# SDRAM.net
KiCad netlist of a schematic drawn in Altium Designer
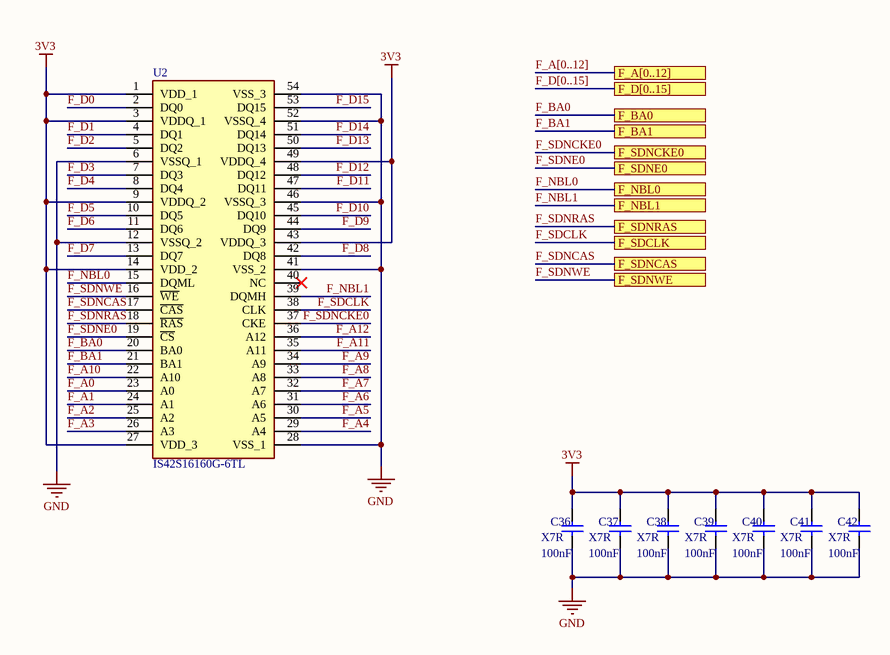
[diagram p0: SDRAM.SchDoc]

(export (version "E")
  (design (tool "Eeschema 10.0.6"))
  (components
    (comp (ref "C36")
      (value "X7R")
      (footprint "1608[0603]")
      (description "Capacitor")
      (fields (field (name "ALTIUM_VALUE") "100nF") (field (name "PUBLISHER") "Altium Limited"))
      (libsource (lib "Miscellaneous Devices") (part "Cap"))
    )
    (comp (ref "C37")
      (value "X7R")
      (footprint "1608[0603]")
      (description "Capacitor")
      (fields (field (name "ALTIUM_VALUE") "100nF") (field (name "PUBLISHER") "Altium Limited"))
      (libsource (lib "Miscellaneous Devices") (part "Cap"))
    )
    (comp (ref "C38")
      (value "X7R")
      (footprint "1608[0603]")
      (description "Capacitor")
      (fields (field (name "ALTIUM_VALUE") "100nF") (field (name "PUBLISHER") "Altium Limited"))
      (libsource (lib "Miscellaneous Devices") (part "Cap"))
    )
    (comp (ref "C39")
      (value "X7R")
      (footprint "1608[0603]")
      (description "Capacitor")
      (fields (field (name "ALTIUM_VALUE") "100nF") (field (name "PUBLISHER") "Altium Limited"))
      (libsource (lib "Miscellaneous Devices") (part "Cap"))
    )
    (comp (ref "C40")
      (value "X7R")
      (footprint "1608[0603]")
      (description "Capacitor")
      (fields (field (name "ALTIUM_VALUE") "100nF") (field (name "PUBLISHER") "Altium Limited"))
      (libsource (lib "Miscellaneous Devices") (part "Cap"))
    )
    (comp (ref "C41")
      (value "X7R")
      (footprint "1608[0603]")
      (description "Capacitor")
      (fields (field (name "ALTIUM_VALUE") "100nF") (field (name "PUBLISHER") "Altium Limited"))
      (libsource (lib "Miscellaneous Devices") (part "Cap"))
    )
    (comp (ref "C42")
      (value "X7R")
      (footprint "1608[0603]")
      (description "Capacitor")
      (fields (field (name "ALTIUM_VALUE") "100nF") (field (name "PUBLISHER") "Altium Limited"))
      (libsource (lib "Miscellaneous Devices") (part "Cap"))
    )
    (comp (ref "U2")
      (value "IS42S16160G-6TL")
      (footprint "SamacSys:SOP80P1176X120-54N")
      (description "Integrated Circuit")
      (fields (field (name "MOUSER PART NUMBER") "870-IS42S16160G-6TL"))
      (libsource (lib "*") (part "IS42S16160G-6TL"))
    )
  )
  (nets
    (net (code "2") (name "/F_A0") (class "Default")
      (node (ref "U2") (pin "23") (pinfunction "A0_23") (pintype "passive"))
    )
    (net (code "3") (name "/F_A1") (class "Default")
      (node (ref "U2") (pin "24") (pinfunction "A1_24") (pintype "passive"))
    )
    (net (code "4") (name "/F_A2") (class "Default")
      (node (ref "U2") (pin "25") (pinfunction "A2_25") (pintype "passive"))
    )
    (net (code "5") (name "/F_A3") (class "Default")
      (node (ref "U2") (pin "26") (pinfunction "A3_26") (pintype "passive"))
    )
    (net (code "6") (name "/F_A4") (class "Default")
      (node (ref "U2") (pin "29") (pinfunction "A4_29") (pintype "passive"))
    )
    (net (code "7") (name "/F_A5") (class "Default")
      (node (ref "U2") (pin "30") (pinfunction "A5_30") (pintype "passive"))
    )
    (net (code "8") (name "/F_A6") (class "Default")
      (node (ref "U2") (pin "31") (pinfunction "A6_31") (pintype "passive"))
    )
    (net (code "9") (name "/F_A7") (class "Default")
      (node (ref "U2") (pin "32") (pinfunction "A7_32") (pintype "passive"))
    )
    (net (code "10") (name "/F_A8") (class "Default")
      (node (ref "U2") (pin "33") (pinfunction "A8_33") (pintype "passive"))
    )
    (net (code "11") (name "/F_A9") (class "Default")
      (node (ref "U2") (pin "34") (pinfunction "A9_34") (pintype "passive"))
    )
    (net (code "12") (name "/F_A10") (class "Default")
      (node (ref "U2") (pin "22") (pinfunction "A10_22") (pintype "passive"))
    )
    (net (code "13") (name "/F_A11") (class "Default")
      (node (ref "U2") (pin "35") (pinfunction "A11_35") (pintype "passive"))
    )
    (net (code "14") (name "/F_A12") (class "Default")
      (node (ref "U2") (pin "36") (pinfunction "A12_36") (pintype "passive"))
    )
    (net (code "16") (name "/F_BA0") (class "Default")
      (node (ref "U2") (pin "20") (pinfunction "BA0_20") (pintype "passive"))
    )
    (net (code "17") (name "/F_BA1") (class "Default")
      (node (ref "U2") (pin "21") (pinfunction "BA1_21") (pintype "passive"))
    )
    (net (code "18") (name "/F_D0") (class "Default")
      (node (ref "U2") (pin "2") (pinfunction "DQ0_2") (pintype "passive"))
    )
    (net (code "19") (name "/F_D1") (class "Default")
      (node (ref "U2") (pin "4") (pinfunction "DQ1_4") (pintype "passive"))
    )
    (net (code "20") (name "/F_D2") (class "Default")
      (node (ref "U2") (pin "5") (pinfunction "DQ2_5") (pintype "passive"))
    )
    (net (code "21") (name "/F_D3") (class "Default")
      (node (ref "U2") (pin "7") (pinfunction "DQ3_7") (pintype "passive"))
    )
    (net (code "22") (name "/F_D4") (class "Default")
      (node (ref "U2") (pin "8") (pinfunction "DQ4_8") (pintype "passive"))
    )
    (net (code "23") (name "/F_D5") (class "Default")
      (node (ref "U2") (pin "10") (pinfunction "DQ5_10") (pintype "passive"))
    )
    (net (code "24") (name "/F_D6") (class "Default")
      (node (ref "U2") (pin "11") (pinfunction "DQ6_11") (pintype "passive"))
    )
    (net (code "25") (name "/F_D7") (class "Default")
      (node (ref "U2") (pin "13") (pinfunction "DQ7_13") (pintype "passive"))
    )
    (net (code "26") (name "/F_D8") (class "Default")
      (node (ref "U2") (pin "42") (pinfunction "DQ8_42") (pintype "passive"))
    )
    (net (code "27") (name "/F_D9") (class "Default")
      (node (ref "U2") (pin "44") (pinfunction "DQ9_44") (pintype "passive"))
    )
    (net (code "28") (name "/F_D10") (class "Default")
      (node (ref "U2") (pin "45") (pinfunction "DQ10_45") (pintype "passive"))
    )
    (net (code "29") (name "/F_D11") (class "Default")
      (node (ref "U2") (pin "47") (pinfunction "DQ11_47") (pintype "passive"))
    )
    (net (code "30") (name "/F_D12") (class "Default")
      (node (ref "U2") (pin "48") (pinfunction "DQ12_48") (pintype "passive"))
    )
    (net (code "31") (name "/F_D13") (class "Default")
      (node (ref "U2") (pin "50") (pinfunction "DQ13_50") (pintype "passive"))
    )
    (net (code "32") (name "/F_D14") (class "Default")
      (node (ref "U2") (pin "51") (pinfunction "DQ14_51") (pintype "passive"))
    )
    (net (code "33") (name "/F_D15") (class "Default")
      (node (ref "U2") (pin "53") (pinfunction "DQ15_53") (pintype "passive"))
    )
    (net (code "35") (name "/F_NBL0") (class "Default")
      (node (ref "U2") (pin "15") (pinfunction "DQML_15") (pintype "passive"))
    )
    (net (code "36") (name "/F_NBL1") (class "Default")
      (node (ref "U2") (pin "39") (pinfunction "DQMH_39") (pintype "passive"))
    )
    (net (code "37") (name "/F_SDCLK") (class "Default")
      (node (ref "U2") (pin "38") (pinfunction "CLK_38") (pintype "passive"))
    )
    (net (code "38") (name "/F_SDNCAS") (class "Default")
      (node (ref "U2") (pin "17") (pinfunction "~{CAS}_17") (pintype "passive"))
    )
    (net (code "39") (name "/F_SDNCKE0") (class "Default")
      (node (ref "U2") (pin "37") (pinfunction "CKE_37") (pintype "passive"))
    )
    (net (code "40") (name "/F_SDNE0") (class "Default")
      (node (ref "U2") (pin "19") (pinfunction "~{CS}_19") (pintype "passive"))
    )
    (net (code "41") (name "/F_SDNRAS") (class "Default")
      (node (ref "U2") (pin "18") (pinfunction "~{RAS}_18") (pintype "passive"))
    )
    (net (code "42") (name "/F_SDNWE") (class "Default")
      (node (ref "U2") (pin "16") (pinfunction "~{WE}_16") (pintype "passive"))
    )
    (net (code "43") (name "3V3") (class "Default")
      (node (ref "C36") (pin "2") (pinfunction "2_2") (pintype "passive"))
      (node (ref "C37") (pin "2") (pinfunction "2_2") (pintype "passive"))
      (node (ref "C38") (pin "2") (pinfunction "2_2") (pintype "passive"))
      (node (ref "C39") (pin "2") (pinfunction "2_2") (pintype "passive"))
      (node (ref "C40") (pin "2") (pinfunction "2_2") (pintype "passive"))
      (node (ref "C41") (pin "2") (pinfunction "2_2") (pintype "passive"))
      (node (ref "C42") (pin "2") (pinfunction "2_2") (pintype "passive"))
      (node (ref "U2") (pin "1") (pinfunction "VDD_1_1") (pintype "passive"))
      (node (ref "U2") (pin "14") (pinfunction "VDD_2_14") (pintype "passive"))
      (node (ref "U2") (pin "27") (pinfunction "VDD_3_27") (pintype "passive"))
      (node (ref "U2") (pin "3") (pinfunction "VDDQ_1_3") (pintype "passive"))
      (node (ref "U2") (pin "43") (pinfunction "VDDQ_3_43") (pintype "passive"))
      (node (ref "U2") (pin "49") (pinfunction "VDDQ_4_49") (pintype "passive"))
      (node (ref "U2") (pin "9") (pinfunction "VDDQ_2_9") (pintype "passive"))
    )
    (net (code "44") (name "GND") (class "Default")
      (node (ref "C36") (pin "1") (pinfunction "1_1") (pintype "passive"))
      (node (ref "C37") (pin "1") (pinfunction "1_1") (pintype "passive"))
      (node (ref "C38") (pin "1") (pinfunction "1_1") (pintype "passive"))
      (node (ref "C39") (pin "1") (pinfunction "1_1") (pintype "passive"))
      (node (ref "C40") (pin "1") (pinfunction "1_1") (pintype "passive"))
      (node (ref "C41") (pin "1") (pinfunction "1_1") (pintype "passive"))
      (node (ref "C42") (pin "1") (pinfunction "1_1") (pintype "passive"))
      (node (ref "U2") (pin "12") (pinfunction "VSSQ_2_12") (pintype "passive"))
      (node (ref "U2") (pin "28") (pinfunction "VSS_1_28") (pintype "passive"))
      (node (ref "U2") (pin "41") (pinfunction "VSS_2_41") (pintype "passive"))
      (node (ref "U2") (pin "46") (pinfunction "VSSQ_3_46") (pintype "passive"))
      (node (ref "U2") (pin "52") (pinfunction "VSSQ_4_52") (pintype "passive"))
      (node (ref "U2") (pin "54") (pinfunction "VSS_3_54") (pintype "passive"))
      (node (ref "U2") (pin "6") (pinfunction "VSSQ_1_6") (pintype "passive"))
    )
    (net (code "45") (name "unconnected-(U2-NC-Pad40)") (class "Default")
      (node (ref "U2") (pin "40") (pinfunction "NC_40") (pintype "passive+no_connect"))
    )
  )
)
